# Button.net
KiCad netlist of a schematic drawn in EAGLE
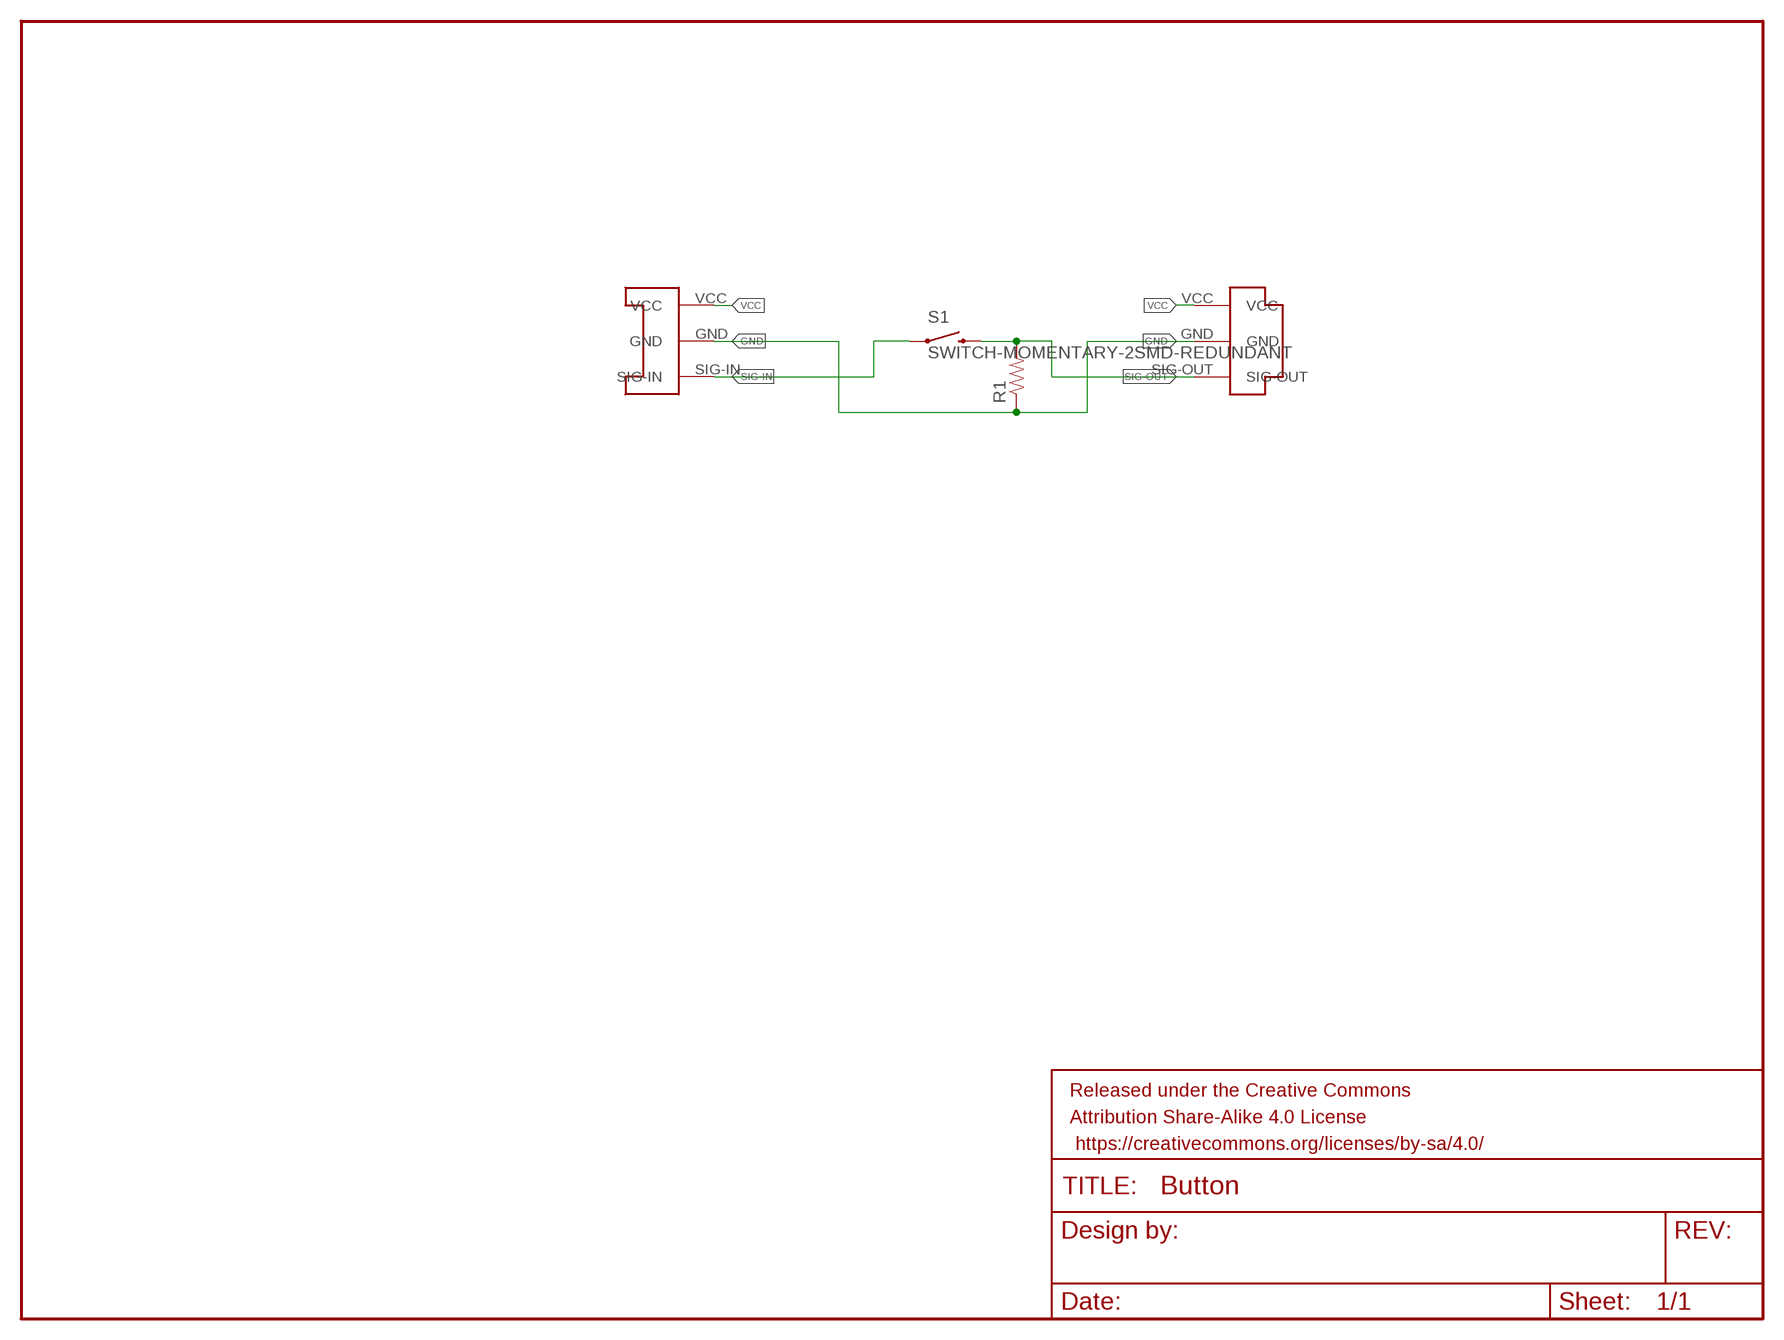
[diagram p0: schematic, sheet 1]

(export (version "E")
  (design (tool "Eeschema 10.0.6"))
  (components
    (comp (ref "FRAME1")
      (value "FRAME-LETTERNO_PACKAGE")
      (footprint "eagle-import:DUMMY")
      (fields (field (name "DESIGNER") "Nobody"))
      (libsource (lib "eagle-import") (part "FRAME-LETTERNO_PACKAGE"))
    )
    (comp (ref "R1")
      (value "RESISTOR0603")
      (footprint "eagle-import:0603-RES")
      (libsource (lib "eagle-import") (part "RESISTOR0603"))
    )
    (comp (ref "S1")
      (value "SWITCH-MOMENTARY-2SMD-REDUNDANT")
      (footprint "eagle-import:TACTILE-SWITCH-SMD")
      (libsource (lib "eagle-import") (part "SWITCH-MOMENTARY-2SMD-REDUNDANT"))
    )
    (comp (ref "U$1")
      (value "CONN-PLUG-3POS-3MM")
      (footprint "eagle-import:PLUG-3POS-3MM-SMD")
      (libsource (lib "eagle-import") (part "CONN-PLUG-3POS-3MM"))
    )
    (comp (ref "U$2")
      (value "CONN-SOCKET-3POS-3MM")
      (footprint "eagle-import:SOCKET-3POS-3MM-SMD")
      (libsource (lib "eagle-import") (part "CONN-SOCKET-3POS-3MM"))
    )
  )
  (nets
    (net (code "1") (name "GND") (class "Default")
      (node (ref "R1") (pin "1") (pinfunction "1_1") (pintype "passive"))
      (node (ref "U$1") (pin "GND") (pinfunction "GND_GND") (pintype "power_in"))
      (node (ref "U$2") (pin "GND") (pinfunction "GND_GND") (pintype "power_in"))
    )
    (net (code "2") (name "SIG-IN") (class "Default")
      (node (ref "S1") (pin "1") (pinfunction "1_1") (pintype "passive"))
      (node (ref "S1") (pin "2") (pinfunction "1_2") (pintype "passive"))
      (node (ref "U$2") (pin "SIG-IN") (pinfunction "SIG-IN_SIG-IN") (pintype "bidirectional"))
    )
    (net (code "3") (name "SIG-OUT") (class "Default")
      (node (ref "R1") (pin "2") (pinfunction "2_2") (pintype "passive"))
      (node (ref "S1") (pin "3") (pinfunction "2_3") (pintype "passive"))
      (node (ref "S1") (pin "4") (pinfunction "2_4") (pintype "passive"))
      (node (ref "U$1") (pin "SIG-OUT") (pinfunction "SIG-OUT_SIG-OUT") (pintype "bidirectional"))
    )
    (net (code "4") (name "VCC") (class "Default")
      (node (ref "U$1") (pin "VCC") (pinfunction "VCC_VCC") (pintype "power_in"))
      (node (ref "U$2") (pin "VCC") (pinfunction "VCC_VCC") (pintype "power_in"))
    )
  )
)
